# KEYWAVE_STARTER.net
KiCad netlist of a schematic drawn in EAGLE
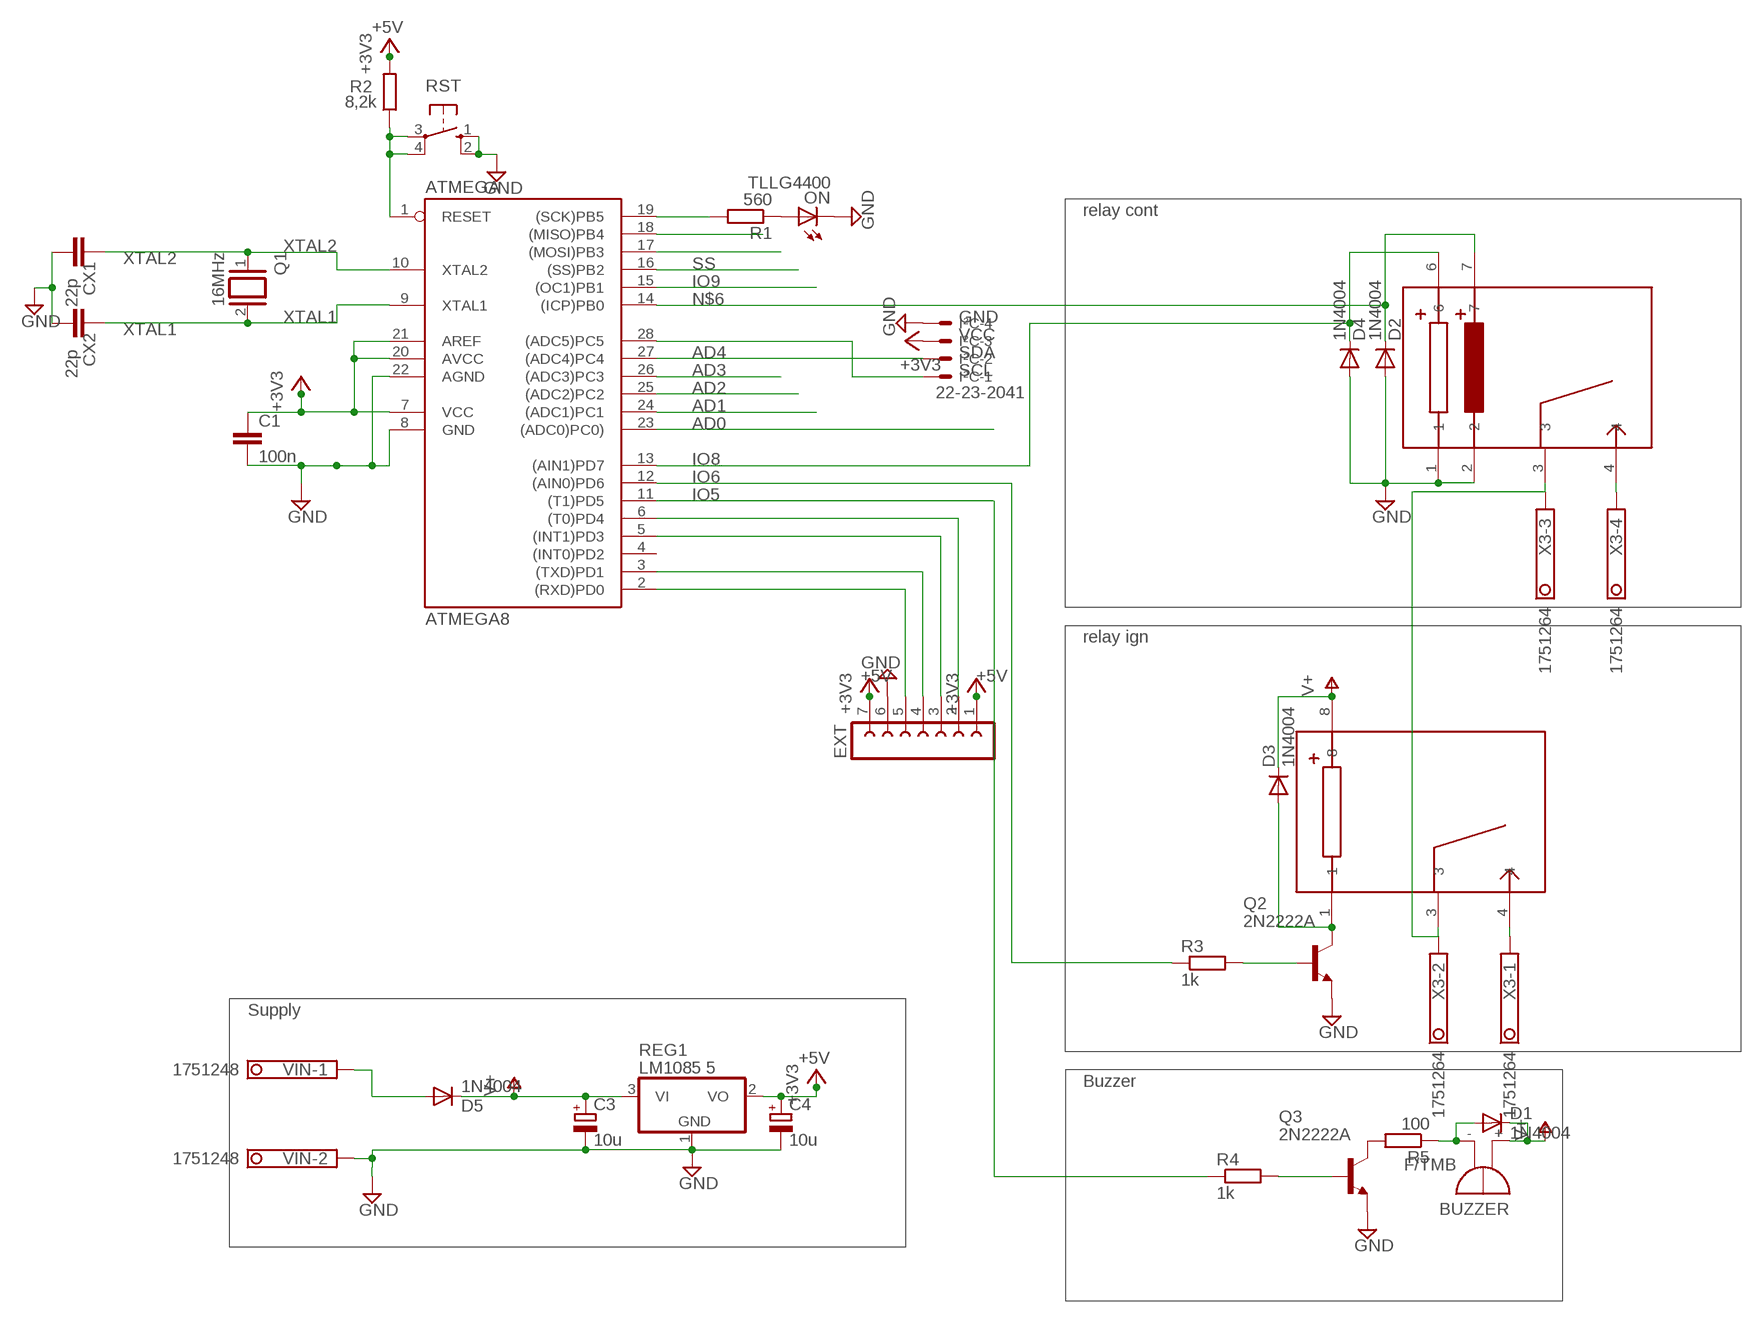
[diagram p0: schematic, sheet 1]

(export (version "E")
  (design (tool "Eeschema 10.0.6"))
  (components
    (comp (ref "ATMEGA")
      (value "ATMEGA8")
      (footprint "eagle-import:DIL28-3")
      (libsource (lib "eagle-import") (part "AT90S4433P"))
    )
    (comp (ref "BUZZER")
      (value "F/TMB")
      (footprint "eagle-import:F_TMB")
      (libsource (lib "eagle-import") (part "F/TMB"))
    )
    (comp (ref "C1")
      (value "100n")
      (footprint "eagle-import:C050-030X075")
      (libsource (lib "eagle-import") (part "rcl_C-EU050-030X075"))
    )
    (comp (ref "C3")
      (value "10u")
      (footprint "eagle-import:E5-6")
      (libsource (lib "eagle-import") (part "CPOL-EUE5-6"))
    )
    (comp (ref "C4")
      (value "10u")
      (footprint "eagle-import:E5-6")
      (libsource (lib "eagle-import") (part "CPOL-EUE5-6"))
    )
    (comp (ref "CONTACT")
      (value "D6BK-1114P")
      (footprint "eagle-import:D6BK-1114C")
      (libsource (lib "eagle-import") (part "D6BK-1114P"))
    )
    (comp (ref "CX1")
      (value "22p")
      (footprint "eagle-import:C0603-ROUND")
      (libsource (lib "eagle-import") (part "C-EU0603-RND"))
    )
    (comp (ref "CX2")
      (value "22p")
      (footprint "eagle-import:C0603-ROUND")
      (libsource (lib "eagle-import") (part "C-EU0603-RND"))
    )
    (comp (ref "D1")
      (value "1N4004")
      (footprint "eagle-import:DO41-10")
      (libsource (lib "eagle-import") (part "1N4004"))
    )
    (comp (ref "D2")
      (value "1N4004")
      (footprint "eagle-import:DO41-10")
      (libsource (lib "eagle-import") (part "1N4004"))
    )
    (comp (ref "D3")
      (value "1N4004")
      (footprint "eagle-import:DO41-10")
      (libsource (lib "eagle-import") (part "1N4004"))
    )
    (comp (ref "D4")
      (value "1N4004")
      (footprint "eagle-import:DO41-10")
      (libsource (lib "eagle-import") (part "1N4004"))
    )
    (comp (ref "D5")
      (value "1N4004")
      (footprint "eagle-import:DO41-10")
      (libsource (lib "eagle-import") (part "1N4004"))
    )
    (comp (ref "EXT")
      (value "FE07-1")
      (footprint "eagle-import:FE07")
      (libsource (lib "eagle-import") (part "FE07-1"))
    )
    (comp (ref "I²C")
      (value "22-23-2041")
      (footprint "eagle-import:22-23-2041")
      (fields (field (name "MF") "MOLEX"))
      (libsource (lib "eagle-import") (part "22-23-2041"))
    )
    (comp (ref "ON")
      (value "TLLG4400")
      (footprint "eagle-import:LED3MM")
      (fields (field (name "MF") "VISHAY SEMICONDUCTOR"))
      (libsource (lib "eagle-import") (part "TLLG4400"))
    )
    (comp (ref "Q1")
      (value "16MHz")
      (footprint "eagle-import:QS")
      (libsource (lib "eagle-import") (part "XTAL/S"))
    )
    (comp (ref "Q2")
      (value "2N2222A")
      (footprint "eagle-import:TO18")
      (libsource (lib "eagle-import") (part "2N2222A"))
    )
    (comp (ref "Q3")
      (value "2N2222A")
      (footprint "eagle-import:TO18")
      (libsource (lib "eagle-import") (part "2N2222A"))
    )
    (comp (ref "R1")
      (value "560")
      (footprint "eagle-import:0207_10")
      (libsource (lib "eagle-import") (part "R-EU_0207/10"))
    )
    (comp (ref "R2")
      (value "8,2k")
      (footprint "eagle-import:0207_10")
      (libsource (lib "eagle-import") (part "R-EU_0207/10"))
    )
    (comp (ref "R3")
      (value "1k")
      (footprint "eagle-import:0207_10")
      (libsource (lib "eagle-import") (part "R-EU_0207/10"))
    )
    (comp (ref "R4")
      (value "1k")
      (footprint "eagle-import:0207_10")
      (libsource (lib "eagle-import") (part "R-EU_0207/10"))
    )
    (comp (ref "R5")
      (value "100")
      (footprint "eagle-import:0207_10")
      (libsource (lib "eagle-import") (part "R-EU_0207/10"))
    )
    (comp (ref "REG1")
      (value "LM1085 5")
      (footprint "eagle-import:TO220")
      (libsource (lib "eagle-import") (part "LM1086?-CT3.3"))
    )
    (comp (ref "RST")
      (value "10-XX")
      (footprint "eagle-import:B3F-10XX")
      (fields (field (name "MPN") "B3F-1000"))
      (libsource (lib "eagle-import") (part "10-XX"))
    )
    (comp (ref "STARTER")
      (value "DK1-L1-12V")
      (footprint "eagle-import:DK1-L1-12V")
      (libsource (lib "eagle-import") (part "DK1-L1-12V"))
    )
    (comp (ref "VIN")
      (value "1751248")
      (footprint "eagle-import:1751248")
      (libsource (lib "eagle-import") (part "1751248"))
    )
    (comp (ref "X3")
      (value "1751264")
      (footprint "eagle-import:1751264")
      (libsource (lib "eagle-import") (part "1751264"))
    )
  )
  (nets
    (net (code "1") (name "+3V3") (class "Default")
      (node (ref "ATMEGA") (pin "20") (pinfunction "AVCC_20") (pintype "power_in"))
      (node (ref "ATMEGA") (pin "21") (pinfunction "AREF_21") (pintype "passive"))
      (node (ref "ATMEGA") (pin "7") (pinfunction "VCC_7") (pintype "power_in"))
      (node (ref "C1") (pin "1") (pinfunction "1_1") (pintype "passive"))
      (node (ref "C4") (pin "+") (pinfunction "+_+") (pintype "passive"))
      (node (ref "EXT") (pin "1") (pinfunction "1_1") (pintype "passive"))
      (node (ref "EXT") (pin "7") (pinfunction "7_7") (pintype "passive"))
      (node (ref "I²C") (pin "3") (pinfunction "S_3") (pintype "passive"))
      (node (ref "R2") (pin "2") (pinfunction "2_2") (pintype "passive"))
      (node (ref "REG1") (pin "2") (pinfunction "VO_2") (pintype "passive"))
    )
    (net (code "2") (name "/AD0") (class "Default")
      (node (ref "ATMEGA") (pin "23") (pinfunction "(ADC0)PC0)_23") (pintype "bidirectional"))
    )
    (net (code "3") (name "/AD1") (class "Default")
      (node (ref "ATMEGA") (pin "24") (pinfunction "(ADC1)PC1_24") (pintype "bidirectional"))
    )
    (net (code "4") (name "/AD2") (class "Default")
      (node (ref "ATMEGA") (pin "25") (pinfunction "(ADC2)PC2_25") (pintype "bidirectional"))
    )
    (net (code "5") (name "/AD3") (class "Default")
      (node (ref "ATMEGA") (pin "26") (pinfunction "(ADC3)PC3_26") (pintype "bidirectional"))
    )
    (net (code "6") (name "/AD4") (class "Default")
      (node (ref "ATMEGA") (pin "27") (pinfunction "(ADC4)PC4_27") (pintype "bidirectional"))
      (node (ref "I²C") (pin "2") (pinfunction "S_2") (pintype "passive"))
    )
    (net (code "7") (name "/IO5") (class "Default")
      (node (ref "ATMEGA") (pin "11") (pinfunction "(T1)PD5_11") (pintype "bidirectional"))
      (node (ref "R4") (pin "1") (pinfunction "1_1") (pintype "passive"))
    )
    (net (code "8") (name "/IO6") (class "Default")
      (node (ref "ATMEGA") (pin "12") (pinfunction "(AIN0)PD6_12") (pintype "bidirectional"))
      (node (ref "R3") (pin "1") (pinfunction "1_1") (pintype "passive"))
    )
    (net (code "9") (name "/IO8") (class "Default")
      (node (ref "ATMEGA") (pin "13") (pinfunction "(AIN1)PD7_13") (pintype "bidirectional"))
      (node (ref "CONTACT") (pin "6") (pinfunction "6_6") (pintype "bidirectional"))
      (node (ref "D4") (pin "C") (pinfunction "C_C") (pintype "passive"))
    )
    (net (code "10") (name "/IO9") (class "Default")
      (node (ref "ATMEGA") (pin "15") (pinfunction "(OC1)PB1_15") (pintype "bidirectional"))
    )
    (net (code "11") (name "/N$6") (class "Default")
      (node (ref "ATMEGA") (pin "14") (pinfunction "(ICP)PB0_14") (pintype "bidirectional"))
      (node (ref "CONTACT") (pin "7") (pinfunction "7_7") (pintype "bidirectional"))
      (node (ref "D2") (pin "C") (pinfunction "C_C") (pintype "passive"))
    )
    (net (code "12") (name "/SS") (class "Default")
      (node (ref "ATMEGA") (pin "16") (pinfunction "(SS)PB2_16") (pintype "bidirectional"))
    )
    (net (code "13") (name "/XTAL1") (class "Default")
      (node (ref "ATMEGA") (pin "9") (pinfunction "XTAL1_9") (pintype "bidirectional"))
      (node (ref "CX2") (pin "2") (pinfunction "2_2") (pintype "passive"))
      (node (ref "Q1") (pin "2") (pinfunction "2_2") (pintype "passive"))
    )
    (net (code "14") (name "/XTAL2") (class "Default")
      (node (ref "ATMEGA") (pin "10") (pinfunction "XTAL2_10") (pintype "bidirectional"))
      (node (ref "CX1") (pin "2") (pinfunction "2_2") (pintype "passive"))
      (node (ref "Q1") (pin "1") (pinfunction "1_1") (pintype "passive"))
    )
    (net (code "15") (name "GND") (class "Default")
      (node (ref "ATMEGA") (pin "22") (pinfunction "AGND_22") (pintype "power_in"))
      (node (ref "ATMEGA") (pin "8") (pinfunction "GND_8") (pintype "power_in"))
      (node (ref "C1") (pin "2") (pinfunction "2_2") (pintype "passive"))
      (node (ref "C3") (pin "-") (pinfunction "-_-") (pintype "passive"))
      (node (ref "C4") (pin "-") (pinfunction "-_-") (pintype "passive"))
      (node (ref "CONTACT") (pin "1") (pinfunction "1_1") (pintype "bidirectional"))
      (node (ref "CONTACT") (pin "2") (pinfunction "2_2") (pintype "bidirectional"))
      (node (ref "CX1") (pin "1") (pinfunction "1_1") (pintype "passive"))
      (node (ref "CX2") (pin "1") (pinfunction "1_1") (pintype "passive"))
      (node (ref "D2") (pin "A") (pinfunction "A_A") (pintype "passive"))
      (node (ref "D4") (pin "A") (pinfunction "A_A") (pintype "passive"))
      (node (ref "EXT") (pin "6") (pinfunction "6_6") (pintype "passive"))
      (node (ref "I²C") (pin "4") (pinfunction "S_4") (pintype "passive"))
      (node (ref "ON") (pin "K") (pinfunction "C_K") (pintype "passive"))
      (node (ref "Q2") (pin "1") (pinfunction "E_1") (pintype "passive"))
      (node (ref "Q3") (pin "1") (pinfunction "E_1") (pintype "passive"))
      (node (ref "REG1") (pin "1") (pinfunction "GND_1") (pintype "passive"))
      (node (ref "RST") (pin "1") (pinfunction "S_1") (pintype "passive"))
      (node (ref "RST") (pin "2") (pinfunction "S1_2") (pintype "passive"))
      (node (ref "VIN") (pin "2") (pinfunction "K_2") (pintype "passive"))
    )
    (net (code "16") (name "Net-(ATMEGA-(ADC5)PC5)") (class "Default")
      (node (ref "ATMEGA") (pin "28") (pinfunction "(ADC5)PC5_28") (pintype "bidirectional"))
      (node (ref "I²C") (pin "1") (pinfunction "S_1") (pintype "passive"))
    )
    (net (code "17") (name "Net-(ATMEGA-(INT1)PD3)") (class "Default")
      (node (ref "ATMEGA") (pin "5") (pinfunction "(INT1)PD3_5") (pintype "bidirectional"))
      (node (ref "EXT") (pin "3") (pinfunction "3_3") (pintype "passive"))
    )
    (net (code "18") (name "Net-(ATMEGA-(RXD)PD0)") (class "Default")
      (node (ref "ATMEGA") (pin "2") (pinfunction "(RXD)PD0_2") (pintype "bidirectional"))
      (node (ref "EXT") (pin "5") (pinfunction "5_5") (pintype "passive"))
    )
    (net (code "19") (name "Net-(ATMEGA-(SCK)PB5)") (class "Default")
      (node (ref "ATMEGA") (pin "19") (pinfunction "(SCK)PB5_19") (pintype "bidirectional"))
      (node (ref "R1") (pin "2") (pinfunction "2_2") (pintype "passive"))
    )
    (net (code "20") (name "Net-(ATMEGA-(T0)PD4)") (class "Default")
      (node (ref "ATMEGA") (pin "6") (pinfunction "(T0)PD4_6") (pintype "bidirectional"))
      (node (ref "EXT") (pin "2") (pinfunction "2_2") (pintype "passive"))
    )
    (net (code "21") (name "Net-(ATMEGA-(TXD)PD1)") (class "Default")
      (node (ref "ATMEGA") (pin "3") (pinfunction "(TXD)PD1_3") (pintype "bidirectional"))
      (node (ref "EXT") (pin "4") (pinfunction "4_4") (pintype "passive"))
    )
    (net (code "22") (name "Net-(ATMEGA-RESET)") (class "Default")
      (node (ref "ATMEGA") (pin "1") (pinfunction "RESET_1") (pintype "input"))
      (node (ref "R2") (pin "1") (pinfunction "1_1") (pintype "passive"))
      (node (ref "RST") (pin "3") (pinfunction "P_3") (pintype "passive"))
      (node (ref "RST") (pin "4") (pinfunction "P1_4") (pintype "passive"))
    )
    (net (code "23") (name "Net-(BUZZER-Pad-)") (class "Default")
      (node (ref "BUZZER") (pin "-") (pinfunction "-_-") (pintype "passive"))
      (node (ref "D1") (pin "A") (pinfunction "A_A") (pintype "passive"))
      (node (ref "R5") (pin "1") (pinfunction "1_1") (pintype "passive"))
    )
    (net (code "24") (name "Net-(ON-PadA)") (class "Default")
      (node (ref "ON") (pin "A") (pinfunction "A_A") (pintype "passive"))
      (node (ref "R1") (pin "1") (pinfunction "1_1") (pintype "passive"))
    )
    (net (code "25") (name "Net-(Q2-B)") (class "Default")
      (node (ref "Q2") (pin "2") (pinfunction "B_2") (pintype "passive"))
      (node (ref "R3") (pin "2") (pinfunction "2_2") (pintype "passive"))
    )
    (net (code "26") (name "Net-(Q2-C)") (class "Default")
      (node (ref "D3") (pin "A") (pinfunction "A_A") (pintype "passive"))
      (node (ref "Q2") (pin "3") (pinfunction "C_3") (pintype "passive"))
      (node (ref "STARTER") (pin "1") (pinfunction "1_1") (pintype "bidirectional"))
    )
    (net (code "27") (name "Net-(Q3-B)") (class "Default")
      (node (ref "Q3") (pin "2") (pinfunction "B_2") (pintype "passive"))
      (node (ref "R4") (pin "2") (pinfunction "2_2") (pintype "passive"))
    )
    (net (code "28") (name "Net-(Q3-C)") (class "Default")
      (node (ref "Q3") (pin "3") (pinfunction "C_3") (pintype "passive"))
      (node (ref "R5") (pin "2") (pinfunction "2_2") (pintype "passive"))
    )
    (net (code "29") (name "Net-(VINA-K)") (class "Default")
      (node (ref "D5") (pin "A") (pinfunction "A_A") (pintype "passive"))
      (node (ref "VIN") (pin "1") (pinfunction "K_1") (pintype "passive"))
    )
    (net (code "30") (name "Net-(X3A-K)") (class "Default")
      (node (ref "STARTER") (pin "4") (pinfunction "4_4") (pintype "bidirectional"))
      (node (ref "X3") (pin "1") (pinfunction "K_1") (pintype "passive"))
    )
    (net (code "31") (name "Net-(X3B-K)") (class "Default")
      (node (ref "CONTACT") (pin "3") (pinfunction "3_3") (pintype "bidirectional"))
      (node (ref "STARTER") (pin "3") (pinfunction "3_3") (pintype "bidirectional"))
      (node (ref "X3") (pin "2") (pinfunction "K_2") (pintype "passive"))
      (node (ref "X3") (pin "3") (pinfunction "K_3") (pintype "passive"))
    )
    (net (code "32") (name "Net-(X3D-K)") (class "Default")
      (node (ref "CONTACT") (pin "4") (pinfunction "4_4") (pintype "bidirectional"))
      (node (ref "X3") (pin "4") (pinfunction "K_4") (pintype "passive"))
    )
    (net (code "33") (name "V+") (class "Default")
      (node (ref "BUZZER") (pin "+") (pinfunction "+_+") (pintype "passive"))
      (node (ref "C3") (pin "+") (pinfunction "+_+") (pintype "passive"))
      (node (ref "D1") (pin "C") (pinfunction "C_C") (pintype "passive"))
      (node (ref "D3") (pin "C") (pinfunction "C_C") (pintype "passive"))
      (node (ref "D5") (pin "C") (pinfunction "C_C") (pintype "passive"))
      (node (ref "REG1") (pin "3") (pinfunction "VI_3") (pintype "input"))
      (node (ref "STARTER") (pin "8") (pinfunction "8_8") (pintype "bidirectional"))
    )
    (net (code "34") (name "unconnected-(ATMEGA-(INT0)PD2-Pad4)") (class "Default")
      (node (ref "ATMEGA") (pin "4") (pinfunction "(INT0)PD2_4") (pintype "bidirectional"))
    )
    (net (code "35") (name "unconnected-(ATMEGA-(MISO)PB4-Pad18)") (class "Default")
      (node (ref "ATMEGA") (pin "18") (pinfunction "(MISO)PB4_18") (pintype "bidirectional"))
    )
    (net (code "36") (name "unconnected-(ATMEGA-(MOSI)PB3-Pad17)") (class "Default")
      (node (ref "ATMEGA") (pin "17") (pinfunction "(MOSI)PB3_17") (pintype "bidirectional"))
    )
  )
)
